# Analog_Channel_Test.net
KiCad netlist of a schematic drawn in Altium Designer
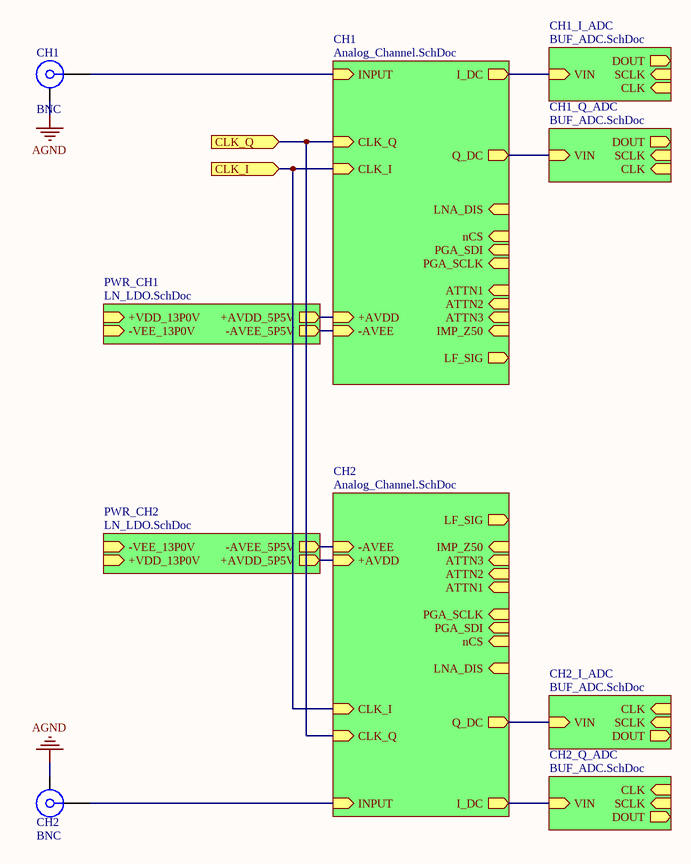
[diagram p0: Analog_Channel_Test.SchDoc]

(export (version "E")
  (design (tool "Eeschema 10.0.6"))
  (components
    (comp (ref "CH1")
      (value "BNC")
      (footprint "BNC-TYCO_1-1337542-0")
      (description "BNC-KE PIN 6.9mm distance")
      (fields (field (name "PARTNUMBER") "51K101-400A4"))
      (libsource (lib "OlvkLib") (part "BNC"))
    )
    (comp (ref "CH2")
      (value "BNC")
      (footprint "BNC-TYCO_1-1337542-0")
      (description "BNC-KE PIN 6.9mm distance")
      (fields (field (name "PARTNUMBER") "51K101-400A4"))
      (libsource (lib "OlvkLib") (part "BNC"))
    )
  )
  (nets
    (net (code "27") (name "/INPUT") (class "Default")
      (node (ref "CH1") (pin "1") (pinfunction "1_1") (pintype "passive"))
    )
    (net (code "28") (name "/INPUT_1") (class "Default")
      (node (ref "CH2") (pin "1") (pinfunction "1_1") (pintype "passive"))
    )
    (net (code "47") (name "AGND") (class "Default")
      (node (ref "CH1") (pin "MH") (pinfunction "MH_MH") (pintype "passive"))
      (node (ref "CH2") (pin "MH") (pinfunction "MH_MH") (pintype "passive"))
    )
  )
)
